# powerboard_v1b.net
KiCad netlist of a schematic drawn in EAGLE
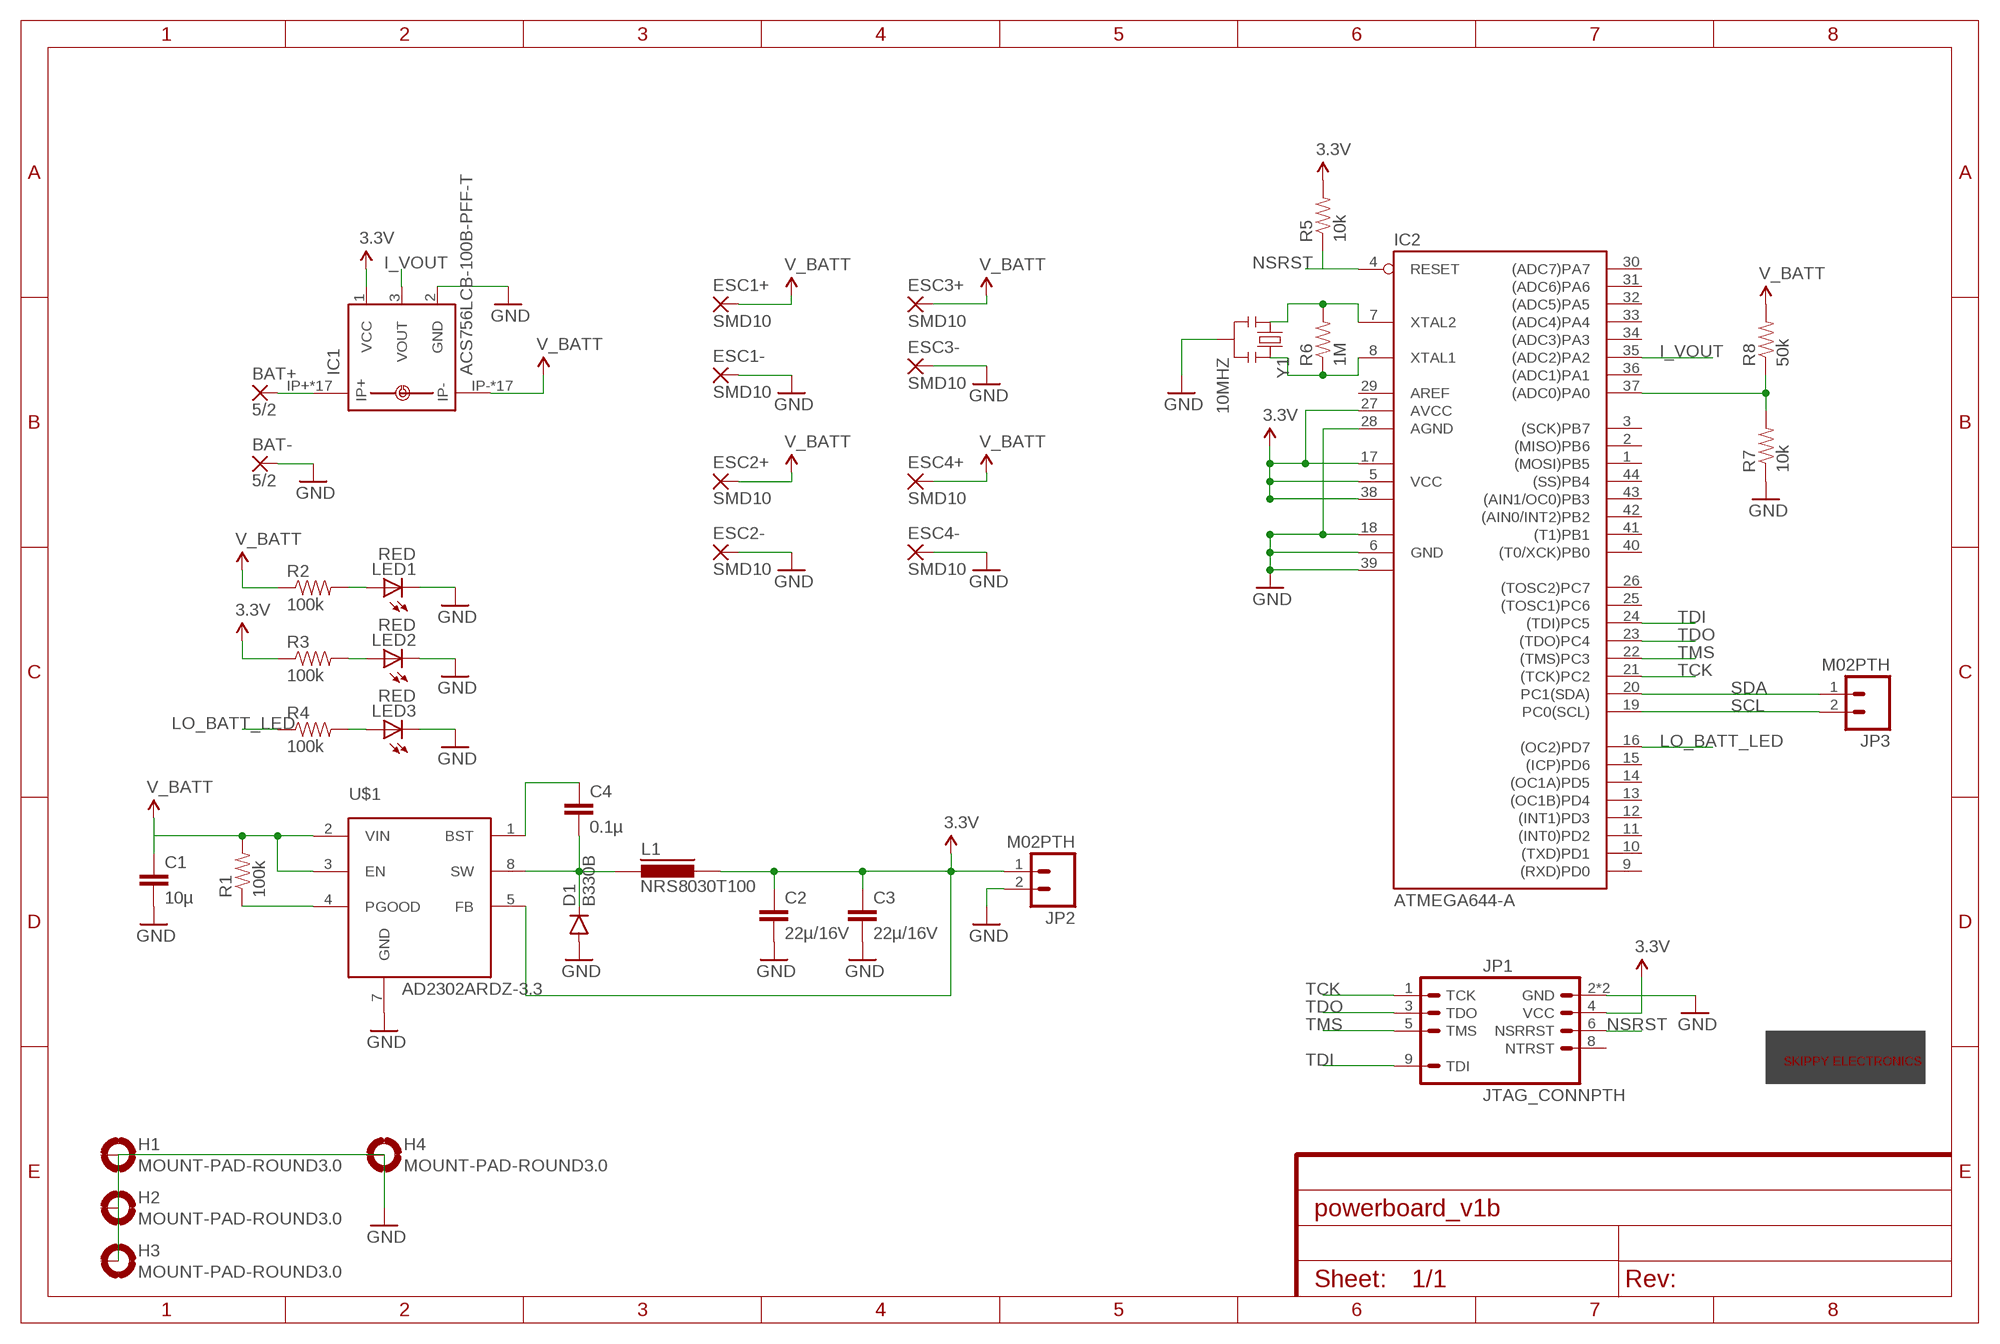
[diagram p0: schematic, sheet 1]

(export (version "E")
  (design (tool "Eeschema 10.0.6"))
  (components
    (comp (ref "BAT+")
      (value "5/2")
      (footprint "eagle-import:5_2")
      (libsource (lib "eagle-import") (part "5/2"))
    )
    (comp (ref "BAT-")
      (value "5/2")
      (footprint "eagle-import:5_2")
      (libsource (lib "eagle-import") (part "5/2"))
    )
    (comp (ref "C1")
      (value "10µ")
      (footprint "eagle-import:1206")
      (libsource (lib "eagle-import") (part "CAP1206"))
    )
    (comp (ref "C2")
      (value "22µ/16V")
      (footprint "eagle-import:1206")
      (libsource (lib "eagle-import") (part "CAP1206"))
    )
    (comp (ref "C3")
      (value "22µ/16V")
      (footprint "eagle-import:1206")
      (libsource (lib "eagle-import") (part "CAP1206"))
    )
    (comp (ref "C4")
      (value "0.1µ")
      (footprint "eagle-import:1206")
      (libsource (lib "eagle-import") (part "CAP1206"))
    )
    (comp (ref "D1")
      (value "B330B")
      (footprint "eagle-import:SMB-DIODE")
      (libsource (lib "eagle-import") (part "DIODESMB"))
    )
    (comp (ref "ESC1+")
      (value "SMD10")
      (footprint "eagle-import:SMD5.08-10.16")
      (libsource (lib "eagle-import") (part "SMD10"))
    )
    (comp (ref "ESC1-")
      (value "SMD10")
      (footprint "eagle-import:SMD5.08-10.16")
      (libsource (lib "eagle-import") (part "SMD10"))
    )
    (comp (ref "ESC2+")
      (value "SMD10")
      (footprint "eagle-import:SMD5.08-10.16")
      (libsource (lib "eagle-import") (part "SMD10"))
    )
    (comp (ref "ESC2-")
      (value "SMD10")
      (footprint "eagle-import:SMD5.08-10.16")
      (libsource (lib "eagle-import") (part "SMD10"))
    )
    (comp (ref "ESC3+")
      (value "SMD10")
      (footprint "eagle-import:SMD5.08-10.16")
      (libsource (lib "eagle-import") (part "SMD10"))
    )
    (comp (ref "ESC3-")
      (value "SMD10")
      (footprint "eagle-import:SMD5.08-10.16")
      (libsource (lib "eagle-import") (part "SMD10"))
    )
    (comp (ref "ESC4+")
      (value "SMD10")
      (footprint "eagle-import:SMD5.08-10.16")
      (libsource (lib "eagle-import") (part "SMD10"))
    )
    (comp (ref "ESC4-")
      (value "SMD10")
      (footprint "eagle-import:SMD5.08-10.16")
      (libsource (lib "eagle-import") (part "SMD10"))
    )
    (comp (ref "H1")
      (value "MOUNT-PAD-ROUND3.0")
      (footprint "eagle-import:3,0-PAD")
      (libsource (lib "eagle-import") (part "MOUNT-PAD-ROUND3.0"))
    )
    (comp (ref "H2")
      (value "MOUNT-PAD-ROUND3.0")
      (footprint "eagle-import:3,0-PAD")
      (libsource (lib "eagle-import") (part "MOUNT-PAD-ROUND3.0"))
    )
    (comp (ref "H3")
      (value "MOUNT-PAD-ROUND3.0")
      (footprint "eagle-import:3,0-PAD")
      (libsource (lib "eagle-import") (part "MOUNT-PAD-ROUND3.0"))
    )
    (comp (ref "H4")
      (value "MOUNT-PAD-ROUND3.0")
      (footprint "eagle-import:3,0-PAD")
      (libsource (lib "eagle-import") (part "MOUNT-PAD-ROUND3.0"))
    )
    (comp (ref "IC1")
      (value "ACS756LCB-100B-PFF-T")
      (footprint "eagle-import:CB-PFF")
      (fields (field (name "MPN") "ACS758LCB-100B-PFF-T"))
      (libsource (lib "eagle-import") (part "ACS756LCB-100B-PFF-T"))
    )
    (comp (ref "IC2")
      (value "ATMEGA644-A")
      (footprint "eagle-import:TQFP44")
      (libsource (lib "eagle-import") (part "ATMEGA644-A"))
    )
    (comp (ref "JP1")
      (value "JTAG_CONNPTH")
      (footprint "eagle-import:AVR_ICSP")
      (libsource (lib "eagle-import") (part "JTAG_CONNPTH"))
    )
    (comp (ref "JP2")
      (value "M02PTH")
      (footprint "eagle-import:1X02")
      (libsource (lib "eagle-import") (part "M02PTH"))
    )
    (comp (ref "JP3")
      (value "M02PTH")
      (footprint "eagle-import:1X02")
      (libsource (lib "eagle-import") (part "M02PTH"))
    )
    (comp (ref "L1")
      (value "NRS8030T100")
      (footprint "eagle-import:NRS8030")
      (libsource (lib "eagle-import") (part "NRS8030T100"))
    )
    (comp (ref "LED1")
      (value "RED")
      (footprint "eagle-import:LED_1206")
      (libsource (lib "eagle-import") (part "LED_E"))
    )
    (comp (ref "LED2")
      (value "RED")
      (footprint "eagle-import:LED_1206")
      (libsource (lib "eagle-import") (part "LED_E"))
    )
    (comp (ref "LED3")
      (value "RED")
      (footprint "eagle-import:LED_1206")
      (libsource (lib "eagle-import") (part "LED_E"))
    )
    (comp (ref "R1")
      (value "100k")
      (footprint "eagle-import:1206")
      (libsource (lib "eagle-import") (part "RESISTOR1206"))
    )
    (comp (ref "R2")
      (value "100k")
      (footprint "eagle-import:1206")
      (libsource (lib "eagle-import") (part "RESISTOR1206"))
    )
    (comp (ref "R3")
      (value "100k")
      (footprint "eagle-import:1206")
      (libsource (lib "eagle-import") (part "RESISTOR1206"))
    )
    (comp (ref "R4")
      (value "100k")
      (footprint "eagle-import:1206")
      (libsource (lib "eagle-import") (part "RESISTOR1206"))
    )
    (comp (ref "R5")
      (value "10k")
      (footprint "eagle-import:1206")
      (libsource (lib "eagle-import") (part "RESISTOR1206"))
    )
    (comp (ref "R6")
      (value "1M")
      (footprint "eagle-import:1206")
      (libsource (lib "eagle-import") (part "RESISTOR1206"))
    )
    (comp (ref "R7")
      (value "10k")
      (footprint "eagle-import:1206")
      (libsource (lib "eagle-import") (part "RESISTOR1206"))
    )
    (comp (ref "R8")
      (value "50k")
      (footprint "eagle-import:1206")
      (libsource (lib "eagle-import") (part "RESISTOR1206"))
    )
    (comp (ref "U$1")
      (value "AD2302ARDZ-3.3")
      (footprint "eagle-import:SO8")
      (libsource (lib "eagle-import") (part "AD2302ARDZ-3.3"))
    )
    (comp (ref "U$2")
      (value "SKIPPYTXT-PLC-10MM")
      (footprint "eagle-import:SKIPPYTXT-PLC-10MM")
      (libsource (lib "eagle-import") (part "SKIPPYTXT-PLC-10MM"))
    )
    (comp (ref "Y1")
      (value "10MHZ")
      (footprint "eagle-import:RESONATOR-SMD")
      (libsource (lib "eagle-import") (part "RESONATOR8MHZ"))
    )
  )
  (nets
    (net (code "1") (name "/I_VOUT") (class "Default")
      (node (ref "IC1") (pin "3") (pinfunction "VOUT_3") (pintype "output"))
      (node (ref "IC2") (pin "35") (pinfunction "(ADC2)PA2_35") (pintype "bidirectional"))
    )
    (net (code "2") (name "/LO_BATT_LED") (class "Default")
      (node (ref "IC2") (pin "16") (pinfunction "(OC2)PD7_16") (pintype "bidirectional"))
      (node (ref "R4") (pin "1") (pinfunction "1_1") (pintype "passive"))
    )
    (net (code "3") (name "/NSRST") (class "Default")
      (node (ref "IC2") (pin "4") (pinfunction "RESET_4") (pintype "input"))
      (node (ref "JP1") (pin "6") (pinfunction "NSRRST_6") (pintype "passive"))
      (node (ref "R5") (pin "1") (pinfunction "1_1") (pintype "passive"))
    )
    (net (code "4") (name "/SCL") (class "Default")
      (node (ref "IC2") (pin "19") (pinfunction "PC0(SCL)_19") (pintype "bidirectional"))
      (node (ref "JP3") (pin "2") (pinfunction "2_2") (pintype "passive"))
    )
    (net (code "5") (name "/SDA") (class "Default")
      (node (ref "IC2") (pin "20") (pinfunction "PC1(SDA)_20") (pintype "bidirectional"))
      (node (ref "JP3") (pin "1") (pinfunction "1_1") (pintype "passive"))
    )
    (net (code "6") (name "/TCK") (class "Default")
      (node (ref "IC2") (pin "21") (pinfunction "(TCK)PC2_21") (pintype "bidirectional"))
      (node (ref "JP1") (pin "1") (pinfunction "TCK_1") (pintype "passive"))
    )
    (net (code "7") (name "/TDI") (class "Default")
      (node (ref "IC2") (pin "24") (pinfunction "(TDI)PC5_24") (pintype "bidirectional"))
      (node (ref "JP1") (pin "9") (pinfunction "TDI_9") (pintype "passive"))
    )
    (net (code "8") (name "/TDO") (class "Default")
      (node (ref "IC2") (pin "23") (pinfunction "(TDO)PC4_23") (pintype "bidirectional"))
      (node (ref "JP1") (pin "3") (pinfunction "TDO_3") (pintype "passive"))
    )
    (net (code "9") (name "/TMS") (class "Default")
      (node (ref "IC2") (pin "22") (pinfunction "(TMS)PC3_22") (pintype "bidirectional"))
      (node (ref "JP1") (pin "5") (pinfunction "TMS_5") (pintype "passive"))
    )
    (net (code "10") (name "3.3V") (class "Default")
      (node (ref "C2") (pin "1") (pinfunction "1_1") (pintype "passive"))
      (node (ref "C3") (pin "1") (pinfunction "1_1") (pintype "passive"))
      (node (ref "IC1") (pin "1") (pinfunction "VCC_1") (pintype "power_in"))
      (node (ref "IC2") (pin "17") (pinfunction "VCC1_17") (pintype "power_in"))
      (node (ref "IC2") (pin "27") (pinfunction "AVCC_27") (pintype "power_in"))
      (node (ref "IC2") (pin "38") (pinfunction "VCC2_38") (pintype "power_in"))
      (node (ref "IC2") (pin "5") (pinfunction "VCC_5") (pintype "power_in"))
      (node (ref "JP1") (pin "4") (pinfunction "VCC_4") (pintype "passive"))
      (node (ref "JP2") (pin "1") (pinfunction "1_1") (pintype "passive"))
      (node (ref "L1") (pin "P$2") (pinfunction "2_P$2") (pintype "passive"))
      (node (ref "R3") (pin "1") (pinfunction "1_1") (pintype "passive"))
      (node (ref "R5") (pin "2") (pinfunction "2_2") (pintype "passive"))
      (node (ref "U$1") (pin "5") (pinfunction "FB_5") (pintype "input"))
    )
    (net (code "11") (name "GND") (class "Default")
      (node (ref "BAT-") (pin "P$1") (pinfunction "P_P$1") (pintype "passive"))
      (node (ref "C1") (pin "2") (pinfunction "2_2") (pintype "passive"))
      (node (ref "C2") (pin "2") (pinfunction "2_2") (pintype "passive"))
      (node (ref "C3") (pin "2") (pinfunction "2_2") (pintype "passive"))
      (node (ref "D1") (pin "A") (pinfunction "A_A") (pintype "passive"))
      (node (ref "ESC1-") (pin "P$1") (pinfunction "P_P$1") (pintype "passive"))
      (node (ref "ESC1-") (pin "P$2") (pinfunction "P_P$2") (pintype "passive"))
      (node (ref "ESC2-") (pin "P$1") (pinfunction "P_P$1") (pintype "passive"))
      (node (ref "ESC2-") (pin "P$2") (pinfunction "P_P$2") (pintype "passive"))
      (node (ref "ESC3-") (pin "P$1") (pinfunction "P_P$1") (pintype "passive"))
      (node (ref "ESC3-") (pin "P$2") (pinfunction "P_P$2") (pintype "passive"))
      (node (ref "ESC4-") (pin "P$1") (pinfunction "P_P$1") (pintype "passive"))
      (node (ref "ESC4-") (pin "P$2") (pinfunction "P_P$2") (pintype "passive"))
      (node (ref "IC1") (pin "2") (pinfunction "GND_2") (pintype "power_in"))
      (node (ref "IC2") (pin "18") (pinfunction "GND1_18") (pintype "power_in"))
      (node (ref "IC2") (pin "28") (pinfunction "AGND_28") (pintype "power_in"))
      (node (ref "IC2") (pin "39") (pinfunction "GND2_39") (pintype "power_in"))
      (node (ref "IC2") (pin "6") (pinfunction "GND_6") (pintype "power_in"))
      (node (ref "JP1") (pin "10") (pinfunction "GND_10") (pintype "power_in"))
      (node (ref "JP1") (pin "2") (pinfunction "GND_2") (pintype "power_in"))
      (node (ref "JP2") (pin "2") (pinfunction "2_2") (pintype "passive"))
      (node (ref "LED1") (pin "C") (pinfunction "C_C") (pintype "passive"))
      (node (ref "LED2") (pin "C") (pinfunction "C_C") (pintype "passive"))
      (node (ref "LED3") (pin "C") (pinfunction "C_C") (pintype "passive"))
      (node (ref "R7") (pin "1") (pinfunction "1_1") (pintype "passive"))
      (node (ref "U$1") (pin "7") (pinfunction "GND_7") (pintype "power_in"))
      (node (ref "Y1") (pin "2") (pinfunction "2_2") (pintype "passive"))
    )
    (net (code "12") (name "Net-(BAT+-P)") (class "Default")
      (node (ref "BAT+") (pin "P$1") (pinfunction "P_P$1") (pintype "passive"))
      (node (ref "IC1") (pin "IP+") (pinfunction "IP+_IP+") (pintype "passive"))
      (node (ref "IC1") (pin "IP+@10") (pinfunction "IP+_IP+@10") (pintype "passive"))
      (node (ref "IC1") (pin "IP+@11") (pinfunction "IP+_IP+@11") (pintype "passive"))
      (node (ref "IC1") (pin "IP+@12") (pinfunction "IP+_IP+@12") (pintype "passive"))
      (node (ref "IC1") (pin "IP+@13") (pinfunction "IP+_IP+@13") (pintype "passive"))
      (node (ref "IC1") (pin "IP+@14") (pinfunction "IP+_IP+@14") (pintype "passive"))
      (node (ref "IC1") (pin "IP+@15") (pinfunction "IP+_IP+@15") (pintype "passive"))
      (node (ref "IC1") (pin "IP+@16") (pinfunction "IP+_IP+@16") (pintype "passive"))
      (node (ref "IC1") (pin "IP+@17") (pinfunction "IP+_IP+@17") (pintype "passive"))
      (node (ref "IC1") (pin "IP+@2") (pinfunction "IP+_IP+@2") (pintype "passive"))
      (node (ref "IC1") (pin "IP+@3") (pinfunction "IP+_IP+@3") (pintype "passive"))
      (node (ref "IC1") (pin "IP+@4") (pinfunction "IP+_IP+@4") (pintype "passive"))
      (node (ref "IC1") (pin "IP+@5") (pinfunction "IP+_IP+@5") (pintype "passive"))
      (node (ref "IC1") (pin "IP+@6") (pinfunction "IP+_IP+@6") (pintype "passive"))
      (node (ref "IC1") (pin "IP+@7") (pinfunction "IP+_IP+@7") (pintype "passive"))
      (node (ref "IC1") (pin "IP+@8") (pinfunction "IP+_IP+@8") (pintype "passive"))
      (node (ref "IC1") (pin "IP+@9") (pinfunction "IP+_IP+@9") (pintype "passive"))
    )
    (net (code "13") (name "Net-(IC2-(ADC0)PA0)") (class "Default")
      (node (ref "IC2") (pin "37") (pinfunction "(ADC0)PA0_37") (pintype "bidirectional"))
      (node (ref "R7") (pin "2") (pinfunction "2_2") (pintype "passive"))
      (node (ref "R8") (pin "1") (pinfunction "1_1") (pintype "passive"))
    )
    (net (code "14") (name "Net-(IC2-XTAL1)") (class "Default")
      (node (ref "IC2") (pin "8") (pinfunction "XTAL1_8") (pintype "bidirectional"))
      (node (ref "R6") (pin "1") (pinfunction "1_1") (pintype "passive"))
      (node (ref "Y1") (pin "3") (pinfunction "3_3") (pintype "passive"))
    )
    (net (code "15") (name "Net-(IC2-XTAL2)") (class "Default")
      (node (ref "IC2") (pin "7") (pinfunction "XTAL2_7") (pintype "bidirectional"))
      (node (ref "R6") (pin "2") (pinfunction "2_2") (pintype "passive"))
      (node (ref "Y1") (pin "1") (pinfunction "1_1") (pintype "passive"))
    )
    (net (code "16") (name "Net-(L1-1)") (class "Default")
      (node (ref "C4") (pin "2") (pinfunction "2_2") (pintype "passive"))
      (node (ref "D1") (pin "C") (pinfunction "C_C") (pintype "passive"))
      (node (ref "L1") (pin "P$1") (pinfunction "1_P$1") (pintype "passive"))
      (node (ref "U$1") (pin "8") (pinfunction "SW_8") (pintype "power_in"))
    )
    (net (code "17") (name "Net-(LED1-PadA)") (class "Default")
      (node (ref "LED1") (pin "A") (pinfunction "A_A") (pintype "passive"))
      (node (ref "R2") (pin "2") (pinfunction "2_2") (pintype "passive"))
    )
    (net (code "18") (name "Net-(LED2-PadA)") (class "Default")
      (node (ref "LED2") (pin "A") (pinfunction "A_A") (pintype "passive"))
      (node (ref "R3") (pin "2") (pinfunction "2_2") (pintype "passive"))
    )
    (net (code "19") (name "Net-(LED3-PadA)") (class "Default")
      (node (ref "LED3") (pin "A") (pinfunction "A_A") (pintype "passive"))
      (node (ref "R4") (pin "2") (pinfunction "2_2") (pintype "passive"))
    )
    (net (code "20") (name "Net-(U$1-BST)") (class "Default")
      (node (ref "C4") (pin "1") (pinfunction "1_1") (pintype "passive"))
      (node (ref "U$1") (pin "1") (pinfunction "BST_1") (pintype "power_in"))
    )
    (net (code "21") (name "Net-(U$1-PGOOD)") (class "Default")
      (node (ref "R1") (pin "1") (pinfunction "1_1") (pintype "passive"))
      (node (ref "U$1") (pin "4") (pinfunction "PGOOD_4") (pintype "output"))
    )
    (net (code "22") (name "V_BATT") (class "Default")
      (node (ref "C1") (pin "1") (pinfunction "1_1") (pintype "passive"))
      (node (ref "ESC1+") (pin "P$1") (pinfunction "P_P$1") (pintype "passive"))
      (node (ref "ESC1+") (pin "P$2") (pinfunction "P_P$2") (pintype "passive"))
      (node (ref "ESC2+") (pin "P$1") (pinfunction "P_P$1") (pintype "passive"))
      (node (ref "ESC2+") (pin "P$2") (pinfunction "P_P$2") (pintype "passive"))
      (node (ref "ESC3+") (pin "P$1") (pinfunction "P_P$1") (pintype "passive"))
      (node (ref "ESC3+") (pin "P$2") (pinfunction "P_P$2") (pintype "passive"))
      (node (ref "ESC4+") (pin "P$1") (pinfunction "P_P$1") (pintype "passive"))
      (node (ref "ESC4+") (pin "P$2") (pinfunction "P_P$2") (pintype "passive"))
      (node (ref "IC1") (pin "IP-") (pinfunction "IP-_IP-") (pintype "passive"))
      (node (ref "IC1") (pin "IP-@10") (pinfunction "IP-_IP-@10") (pintype "passive"))
      (node (ref "IC1") (pin "IP-@11") (pinfunction "IP-_IP-@11") (pintype "passive"))
      (node (ref "IC1") (pin "IP-@12") (pinfunction "IP-_IP-@12") (pintype "passive"))
      (node (ref "IC1") (pin "IP-@13") (pinfunction "IP-_IP-@13") (pintype "passive"))
      (node (ref "IC1") (pin "IP-@14") (pinfunction "IP-_IP-@14") (pintype "passive"))
      (node (ref "IC1") (pin "IP-@15") (pinfunction "IP-_IP-@15") (pintype "passive"))
      (node (ref "IC1") (pin "IP-@16") (pinfunction "IP-_IP-@16") (pintype "passive"))
      (node (ref "IC1") (pin "IP-@17") (pinfunction "IP-_IP-@17") (pintype "passive"))
      (node (ref "IC1") (pin "IP-@2") (pinfunction "IP-_IP-@2") (pintype "passive"))
      (node (ref "IC1") (pin "IP-@3") (pinfunction "IP-_IP-@3") (pintype "passive"))
      (node (ref "IC1") (pin "IP-@4") (pinfunction "IP-_IP-@4") (pintype "passive"))
      (node (ref "IC1") (pin "IP-@5") (pinfunction "IP-_IP-@5") (pintype "passive"))
      (node (ref "IC1") (pin "IP-@6") (pinfunction "IP-_IP-@6") (pintype "passive"))
      (node (ref "IC1") (pin "IP-@7") (pinfunction "IP-_IP-@7") (pintype "passive"))
      (node (ref "IC1") (pin "IP-@8") (pinfunction "IP-_IP-@8") (pintype "passive"))
      (node (ref "IC1") (pin "IP-@9") (pinfunction "IP-_IP-@9") (pintype "passive"))
      (node (ref "R1") (pin "2") (pinfunction "2_2") (pintype "passive"))
      (node (ref "R2") (pin "1") (pinfunction "1_1") (pintype "passive"))
      (node (ref "R8") (pin "2") (pinfunction "2_2") (pintype "passive"))
      (node (ref "U$1") (pin "2") (pinfunction "VIN_2") (pintype "power_in"))
      (node (ref "U$1") (pin "3") (pinfunction "EN_3") (pintype "input"))
    )
    (net (code "23") (name "unconnected-(H1-MOUNT-PadB3,0)") (class "Default")
      (node (ref "H1") (pin "B3,0") (pinfunction "MOUNT_B3,0") (pintype "passive"))
    )
    (net (code "24") (name "unconnected-(H2-MOUNT-PadB3,0)") (class "Default")
      (node (ref "H2") (pin "B3,0") (pinfunction "MOUNT_B3,0") (pintype "passive"))
    )
    (net (code "25") (name "unconnected-(H3-MOUNT-PadB3,0)") (class "Default")
      (node (ref "H3") (pin "B3,0") (pinfunction "MOUNT_B3,0") (pintype "passive"))
    )
    (net (code "26") (name "unconnected-(H4-MOUNT-PadB3,0)") (class "Default")
      (node (ref "H4") (pin "B3,0") (pinfunction "MOUNT_B3,0") (pintype "passive"))
    )
    (net (code "27") (name "unconnected-(IC2-(ADC1)PA1-Pad36)") (class "Default")
      (node (ref "IC2") (pin "36") (pinfunction "(ADC1)PA1_36") (pintype "bidirectional"))
    )
    (net (code "28") (name "unconnected-(IC2-(ADC3)PA3-Pad34)") (class "Default")
      (node (ref "IC2") (pin "34") (pinfunction "(ADC3)PA3_34") (pintype "bidirectional"))
    )
    (net (code "29") (name "unconnected-(IC2-(ADC4)PA4-Pad33)") (class "Default")
      (node (ref "IC2") (pin "33") (pinfunction "(ADC4)PA4_33") (pintype "bidirectional"))
    )
    (net (code "30") (name "unconnected-(IC2-(ADC5)PA5-Pad32)") (class "Default")
      (node (ref "IC2") (pin "32") (pinfunction "(ADC5)PA5_32") (pintype "bidirectional"))
    )
    (net (code "31") (name "unconnected-(IC2-(ADC6)PA6-Pad31)") (class "Default")
      (node (ref "IC2") (pin "31") (pinfunction "(ADC6)PA6_31") (pintype "bidirectional"))
    )
    (net (code "32") (name "unconnected-(IC2-(ADC7)PA7-Pad30)") (class "Default")
      (node (ref "IC2") (pin "30") (pinfunction "(ADC7)PA7_30") (pintype "bidirectional"))
    )
    (net (code "33") (name "unconnected-(IC2-(AIN0{slash}INT2)PB2-Pad42)") (class "Default")
      (node (ref "IC2") (pin "42") (pinfunction "(AIN0/INT2)PB2_42") (pintype "bidirectional"))
    )
    (net (code "34") (name "unconnected-(IC2-(AIN1{slash}OC0)PB3-Pad43)") (class "Default")
      (node (ref "IC2") (pin "43") (pinfunction "(AIN1/OC0)PB3_43") (pintype "bidirectional"))
    )
    (net (code "35") (name "unconnected-(IC2-(ICP)PD6-Pad15)") (class "Default")
      (node (ref "IC2") (pin "15") (pinfunction "(ICP)PD6_15") (pintype "bidirectional"))
    )
    (net (code "36") (name "unconnected-(IC2-(INT0)PD2-Pad11)") (class "Default")
      (node (ref "IC2") (pin "11") (pinfunction "(INT0)PD2_11") (pintype "bidirectional"))
    )
    (net (code "37") (name "unconnected-(IC2-(INT1)PD3-Pad12)") (class "Default")
      (node (ref "IC2") (pin "12") (pinfunction "(INT1)PD3_12") (pintype "bidirectional"))
    )
    (net (code "38") (name "unconnected-(IC2-(MISO)PB6-Pad2)") (class "Default")
      (node (ref "IC2") (pin "2") (pinfunction "(MISO)PB6_2") (pintype "bidirectional"))
    )
    (net (code "39") (name "unconnected-(IC2-(MOSI)PB5-Pad1)") (class "Default")
      (node (ref "IC2") (pin "1") (pinfunction "(MOSI)PB5_1") (pintype "bidirectional"))
    )
    (net (code "40") (name "unconnected-(IC2-(OC1A)PD5-Pad14)") (class "Default")
      (node (ref "IC2") (pin "14") (pinfunction "(OC1A)PD5_14") (pintype "bidirectional"))
    )
    (net (code "41") (name "unconnected-(IC2-(OC1B)PD4-Pad13)") (class "Default")
      (node (ref "IC2") (pin "13") (pinfunction "(OC1B)PD4_13") (pintype "bidirectional"))
    )
    (net (code "42") (name "unconnected-(IC2-(RXD)PD0-Pad9)") (class "Default")
      (node (ref "IC2") (pin "9") (pinfunction "(RXD)PD0_9") (pintype "bidirectional"))
    )
    (net (code "43") (name "unconnected-(IC2-(SCK)PB7-Pad3)") (class "Default")
      (node (ref "IC2") (pin "3") (pinfunction "(SCK)PB7_3") (pintype "bidirectional"))
    )
    (net (code "44") (name "unconnected-(IC2-(SS)PB4-Pad44)") (class "Default")
      (node (ref "IC2") (pin "44") (pinfunction "(SS)PB4_44") (pintype "bidirectional"))
    )
    (net (code "45") (name "unconnected-(IC2-(T0{slash}XCK)PB0-Pad40)") (class "Default")
      (node (ref "IC2") (pin "40") (pinfunction "(T0/XCK)PB0_40") (pintype "bidirectional"))
    )
    (net (code "46") (name "unconnected-(IC2-(T1)PB1-Pad41)") (class "Default")
      (node (ref "IC2") (pin "41") (pinfunction "(T1)PB1_41") (pintype "bidirectional"))
    )
    (net (code "47") (name "unconnected-(IC2-(TOSC1)PC6-Pad25)") (class "Default")
      (node (ref "IC2") (pin "25") (pinfunction "(TOSC1)PC6_25") (pintype "bidirectional"))
    )
    (net (code "48") (name "unconnected-(IC2-(TOSC2)PC7-Pad26)") (class "Default")
      (node (ref "IC2") (pin "26") (pinfunction "(TOSC2)PC7_26") (pintype "bidirectional"))
    )
    (net (code "49") (name "unconnected-(IC2-(TXD)PD1-Pad10)") (class "Default")
      (node (ref "IC2") (pin "10") (pinfunction "(TXD)PD1_10") (pintype "bidirectional"))
    )
    (net (code "50") (name "unconnected-(IC2-AREF-Pad29)") (class "Default")
      (node (ref "IC2") (pin "29") (pinfunction "AREF_29") (pintype "passive"))
    )
    (net (code "51") (name "unconnected-(JP1-NTRST-Pad8)") (class "Default")
      (node (ref "JP1") (pin "8") (pinfunction "NTRST_8") (pintype "passive"))
    )
  )
)
